# XentrinoBoard-ESP32-WROOM-2WD-2020_v1_2.net
KiCad netlist of a schematic drawn in EasyEDA
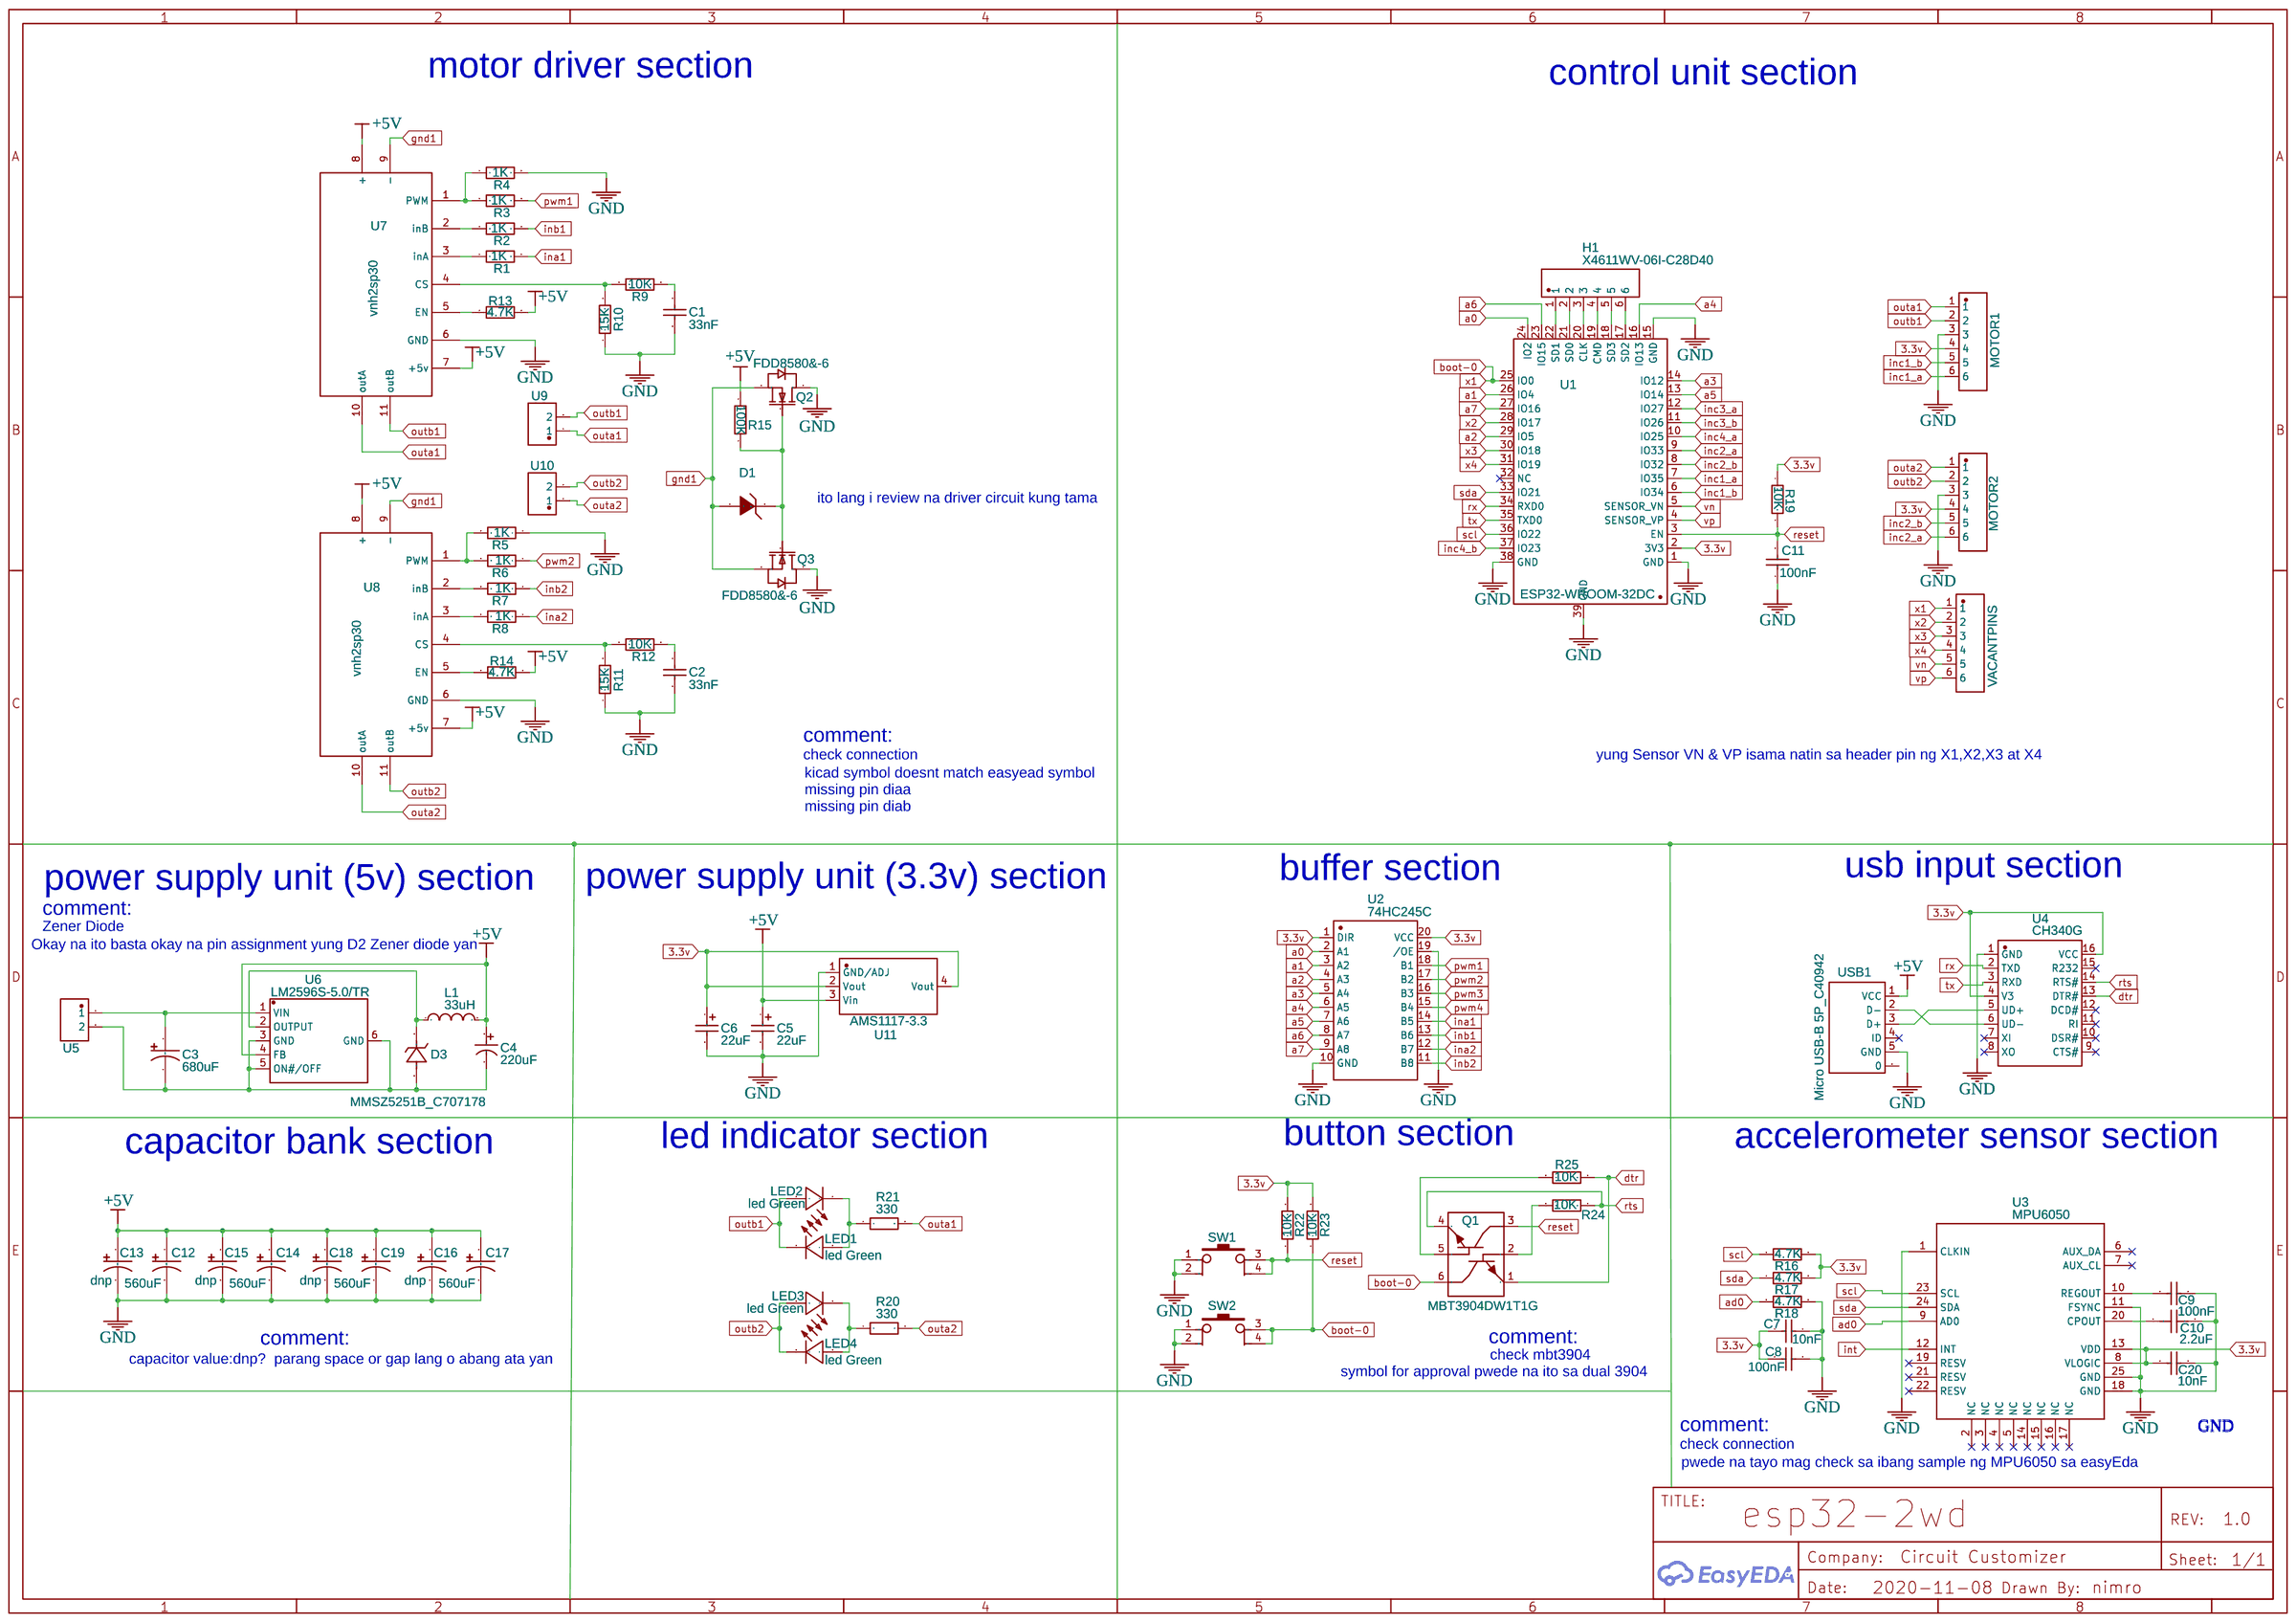
[diagram p0: schematic sheet]

(export (version "E")
  (design (tool "Eeschema 10.0.6"))
  (components
    (comp (ref "C1")
      (value "33nF")
      (fields
        (field (name "BOM_Manufacturer Part") "0805B333K500NT")
        (field (name "BOM_Supplier Part") "C1739")
      )
      (libsource (lib "") (part "0805B333K500NT"))
    )
    (comp (ref "C2")
      (value "33nF")
      (fields
        (field (name "BOM_Manufacturer Part") "0805B333K500NT")
        (field (name "BOM_Supplier Part") "C1739")
      )
      (libsource (lib "") (part "0805B333K500NT"))
    )
    (comp (ref "C3")
      (value "680uF")
      (fields
        (field (name "BOM_Manufacturer Part") "EEEFK1E681SP")
        (field (name "BOM_Supplier Part") "C413667")
      )
      (libsource (lib "") (part "EEEFK1E681SP"))
    )
    (comp (ref "C4")
      (value "220uF")
      (fields
        (field (name "BOM_Manufacturer Part") "DV221M025F105R")
        (field (name "BOM_Supplier Part") "C65222")
      )
      (libsource (lib "") (part "DV221M025F105R"))
    )
    (comp (ref "C5")
      (value "22uF")
      (fields
        (field (name "BOM_Manufacturer Part") "TAJA226K006RNJ")
        (field (name "BOM_Supplier Part") "C7182")
      )
      (libsource (lib "") (part "TAJA226K006RNJ"))
    )
    (comp (ref "C6")
      (value "22uF")
      (fields
        (field (name "BOM_Manufacturer Part") "TAJA226K006RNJ")
        (field (name "BOM_Supplier Part") "C7182")
      )
      (libsource (lib "") (part "TAJA226K006RNJ"))
    )
    (comp (ref "C7")
      (value "10nF")
      (fields
        (field (name "BOM_Manufacturer Part") "CL21C103JBFNNNE")
        (field (name "BOM_Supplier Part") "C27071")
      )
      (libsource (lib "") (part "CL21C103JBFNNNE"))
    )
    (comp (ref "C8")
      (value "100nF")
      (fields
        (field (name "BOM_Manufacturer Part") "CL21B104JBCNNNC")
        (field (name "BOM_Supplier Part") "C62912")
      )
      (libsource (lib "") (part "CL21B104JBCNNNC"))
    )
    (comp (ref "C9")
      (value "100nF")
      (fields
        (field (name "BOM_Manufacturer Part") "CL21B104JBCNNNC")
        (field (name "BOM_Supplier Part") "C62912")
      )
      (libsource (lib "") (part "CL21B104JBCNNNC"))
    )
    (comp (ref "C10")
      (value "2.2uF")
      (fields
        (field (name "BOM_Manufacturer Part") "CL10A225KA8NNNC")
        (field (name "BOM_Supplier Part") "C57895")
      )
      (libsource (lib "") (part "CL10A225KA8NNNC"))
    )
    (comp (ref "C11")
      (value "100nF")
      (fields
        (field (name "BOM_Manufacturer Part") "CL21B104JBCNNNC")
        (field (name "BOM_Supplier Part") "C62912")
      )
      (libsource (lib "") (part "CL21B104JBCNNNC_1"))
    )
    (comp (ref "C12")
      (value "560uF")
      (fields
        (field (name "BOM_Manufacturer Part") "PC0J561ME080A00CR0")
        (field (name "BOM_Supplier Part") "C190902")
      )
      (libsource (lib "") (part "PC0J561ME080A00CR0_1"))
    )
    (comp (ref "C13")
      (value "dnp")
      (fields
        (field (name "BOM_Manufacturer Part") "PC0J561ME080A00CR0")
        (field (name "BOM_Supplier Part") "C190902")
      )
      (libsource (lib "") (part "PC0J561ME080A00CR0_1"))
    )
    (comp (ref "C14")
      (value "560uF")
      (fields
        (field (name "BOM_Manufacturer Part") "PC0J561ME080A00CR0")
        (field (name "BOM_Supplier Part") "C190902")
      )
      (libsource (lib "") (part "PC0J561ME080A00CR0_1"))
    )
    (comp (ref "C15")
      (value "dnp")
      (fields
        (field (name "BOM_Manufacturer Part") "PC0J561ME080A00CR0")
        (field (name "BOM_Supplier Part") "C190902")
      )
      (libsource (lib "") (part "PC0J561ME080A00CR0_1"))
    )
    (comp (ref "C16")
      (value "dnp")
      (fields
        (field (name "BOM_Manufacturer Part") "PC0J561ME080A00CR0")
        (field (name "BOM_Supplier Part") "C190902")
      )
      (libsource (lib "") (part "PC0J561ME080A00CR0"))
    )
    (comp (ref "C17")
      (value "560uF")
      (fields
        (field (name "BOM_Manufacturer Part") "PC0J561ME080A00CR0")
        (field (name "BOM_Supplier Part") "C190902")
      )
      (libsource (lib "") (part "PC0J561ME080A00CR0"))
    )
    (comp (ref "C18")
      (value "dnp")
      (fields
        (field (name "BOM_Manufacturer Part") "PC0J561ME080A00CR0")
        (field (name "BOM_Supplier Part") "C190902")
      )
      (libsource (lib "") (part "PC0J561ME080A00CR0_1"))
    )
    (comp (ref "C19")
      (value "560uF")
      (fields
        (field (name "BOM_Manufacturer Part") "PC0J561ME080A00CR0")
        (field (name "BOM_Supplier Part") "C190902")
      )
      (libsource (lib "") (part "PC0J561ME080A00CR0_1"))
    )
    (comp (ref "C20")
      (value "10nF")
      (fields
        (field (name "BOM_Manufacturer Part") "CL21B104JBCNNNC")
        (field (name "BOM_Supplier Part") "C62912")
      )
      (libsource (lib "") (part "CL21B104JBCNNNC"))
    )
    (comp (ref "D1")
      (value "BZT52C2V7-7-F")
      (fields (field (name "BOM_Supplier Part") "C151624"))
      (libsource (lib "") (part "BZT52C2V7-7-F"))
    )
    (comp (ref "D3")
      (value "MMSZ5251B_C707178")
      (fields (field (name "BOM_Manufacturer Part") "MMSZ5251B") (field (name "BOM_Supplier Part") "C707178"))
      (libsource (lib "") (part "MMSZ5251B_C707178"))
    )
    (comp (ref "H1")
      (value "X4611WV-06I-C28D40")
      (fields (field (name "BOM_Supplier Part") "C706993"))
      (libsource (lib "") (part "X4611WV-06I-C28D40_2"))
    )
    (comp (ref "L1")
      (value "33uH")
      (fields
        (field (name "BOM_Manufacturer Part") "SWPA8040S330MT")
        (field (name "BOM_Supplier Part") "C83467")
      )
      (libsource (lib "") (part "SWPA8040S330MT"))
    )
    (comp (ref "LED1")
      (value "led Green")
      (fields (field (name "BOM_Supplier Part") "C14641"))
      (libsource (lib "") (part "led Green_1"))
    )
    (comp (ref "LED2")
      (value "led Green")
      (fields (field (name "BOM_Supplier Part") "C14641"))
      (libsource (lib "") (part "led Green"))
    )
    (comp (ref "LED3")
      (value "led Green")
      (fields (field (name "BOM_Supplier Part") "C14641"))
      (libsource (lib "") (part "led Green"))
    )
    (comp (ref "LED4")
      (value "led Green")
      (fields (field (name "BOM_Supplier Part") "C14641"))
      (libsource (lib "") (part "led Green_1"))
    )
    (comp (ref "MOTOR1")
      (value "X4611WV-06I-C28D40")
      (fields (field (name "BOM_Supplier Part") "C706993"))
      (libsource (lib "") (part "X4611WV-06I-C28D40"))
    )
    (comp (ref "MOTOR2")
      (value "X4611WV-06I-C28D40")
      (fields (field (name "BOM_Supplier Part") "C706993"))
      (libsource (lib "") (part "X4611WV-06I-C28D40"))
    )
    (comp (ref "Q1")
      (value "MBT3904DW1T1G")
      (fields (field (name "BOM_Supplier Part") "C110150"))
      (libsource (lib "") (part "MBT3904DW1T1G"))
    )
    (comp (ref "Q2")
      (value "FDD8580&-6")
      (fields (field (name "BOM_Supplier Part") "C693389"))
      (libsource (lib "") (part "FDD8580&amp;-6_1"))
    )
    (comp (ref "Q3")
      (value "FDD8580&-6")
      (fields (field (name "BOM_Supplier Part") "C693389"))
      (libsource (lib "") (part "FDD8580&amp;-6"))
    )
    (comp (ref "R1")
      (value "1K")
      (fields
        (field (name "BOM_Manufacturer Part") "RT0805FRD071KL")
        (field (name "BOM_Supplier Part") "C136907")
      )
      (libsource (lib "") (part "RT0805FRD071KL"))
    )
    (comp (ref "R2")
      (value "1K")
      (fields
        (field (name "BOM_Manufacturer Part") "RT0805FRD071KL")
        (field (name "BOM_Supplier Part") "C136907")
      )
      (libsource (lib "") (part "RT0805FRD071KL"))
    )
    (comp (ref "R3")
      (value "1K")
      (fields
        (field (name "BOM_Manufacturer Part") "RT0805FRD071KL")
        (field (name "BOM_Supplier Part") "C136907")
      )
      (libsource (lib "") (part "RT0805FRD071KL"))
    )
    (comp (ref "R4")
      (value "1K")
      (fields
        (field (name "BOM_Manufacturer Part") "RT0805FRD071KL")
        (field (name "BOM_Supplier Part") "C136907")
      )
      (libsource (lib "") (part "RT0805FRD071KL"))
    )
    (comp (ref "R5")
      (value "1K")
      (fields
        (field (name "BOM_Manufacturer Part") "RT0805FRD071KL")
        (field (name "BOM_Supplier Part") "C136907")
      )
      (libsource (lib "") (part "RT0805FRD071KL_1"))
    )
    (comp (ref "R6")
      (value "1K")
      (fields
        (field (name "BOM_Manufacturer Part") "RT0805FRD071KL")
        (field (name "BOM_Supplier Part") "C136907")
      )
      (libsource (lib "") (part "RT0805FRD071KL_1"))
    )
    (comp (ref "R7")
      (value "1K")
      (fields
        (field (name "BOM_Manufacturer Part") "RT0805FRD071KL")
        (field (name "BOM_Supplier Part") "C136907")
      )
      (libsource (lib "") (part "RT0805FRD071KL_1"))
    )
    (comp (ref "R8")
      (value "1K")
      (fields
        (field (name "BOM_Manufacturer Part") "RT0805FRD071KL")
        (field (name "BOM_Supplier Part") "C136907")
      )
      (libsource (lib "") (part "RT0805FRD071KL_1"))
    )
    (comp (ref "R9")
      (value "10K")
      (fields
        (field (name "BOM_Manufacturer Part") "LE03WAJ0103T5E")
        (field (name "BOM_Supplier Part") "C81087")
      )
      (libsource (lib "") (part "LE03WAJ0103T5E"))
    )
    (comp (ref "R10")
      (value "15K")
      (fields
        (field (name "BOM_Manufacturer Part") "RK73H2ATTD1502F")
        (field (name "BOM_Supplier Part") "C160068")
      )
      (libsource (lib "") (part "RK73H2ATTD1502F"))
    )
    (comp (ref "R11")
      (value "15K")
      (fields
        (field (name "BOM_Manufacturer Part") "RK73H2ATTD1502F")
        (field (name "BOM_Supplier Part") "C160068")
      )
      (libsource (lib "") (part "RK73H2ATTD1502F"))
    )
    (comp (ref "R12")
      (value "10K")
      (fields
        (field (name "BOM_Manufacturer Part") "LE03WAJ0103T5E")
        (field (name "BOM_Supplier Part") "C81087")
      )
      (libsource (lib "") (part "LE03WAJ0103T5E"))
    )
    (comp (ref "R13")
      (value "4.7K")
      (fields
        (field (name "BOM_Manufacturer Part") "RC0603JR-074K7L")
        (field (name "BOM_Supplier Part") "C105428")
      )
      (libsource (lib "") (part "RC0603JR-074K7L"))
    )
    (comp (ref "R14")
      (value "4.7K")
      (fields
        (field (name "BOM_Manufacturer Part") "RC0603JR-074K7L")
        (field (name "BOM_Supplier Part") "C105428")
      )
      (libsource (lib "") (part "RC0603JR-074K7L"))
    )
    (comp (ref "R15")
      (value "100K")
      (fields
        (field (name "BOM_Manufacturer Part") "MCWF08U1003BTL")
        (field (name "BOM_Supplier Part") "C241287")
      )
      (libsource (lib "") (part "MCWF08U1003BTL"))
    )
    (comp (ref "R16")
      (value "4.7K")
      (fields
        (field (name "BOM_Manufacturer Part") "RC0603JR-074K7L")
        (field (name "BOM_Supplier Part") "C105428")
      )
      (libsource (lib "") (part "RC0603JR-074K7L"))
    )
    (comp (ref "R17")
      (value "4.7K")
      (fields
        (field (name "BOM_Manufacturer Part") "RC0603JR-074K7L")
        (field (name "BOM_Supplier Part") "C105428")
      )
      (libsource (lib "") (part "RC0603JR-074K7L"))
    )
    (comp (ref "R18")
      (value "4.7K")
      (fields
        (field (name "BOM_Manufacturer Part") "RC0603JR-074K7L")
        (field (name "BOM_Supplier Part") "C105428")
      )
      (libsource (lib "") (part "RC0603JR-074K7L"))
    )
    (comp (ref "R19")
      (value "10K")
      (fields
        (field (name "BOM_Manufacturer Part") "LE03WAJ0103T5E")
        (field (name "BOM_Supplier Part") "C81087")
      )
      (libsource (lib "") (part "LE03WAJ0103T5E_3"))
    )
    (comp (ref "R20")
      (value "330")
      (fields
        (field (name "BOM_Manufacturer Part") "330R 5% 0603")
        (field (name "BOM_Supplier Part") "C22104")
      )
      (libsource (lib "") (part "330R 5% 0603"))
    )
    (comp (ref "R21")
      (value "330")
      (fields
        (field (name "BOM_Manufacturer Part") "330R 5% 0603")
        (field (name "BOM_Supplier Part") "C22104")
      )
      (libsource (lib "") (part "330R 5% 0603"))
    )
    (comp (ref "R22")
      (value "10K")
      (fields
        (field (name "BOM_Manufacturer Part") "LE03WAJ0103T5E")
        (field (name "BOM_Supplier Part") "C81087")
      )
      (libsource (lib "") (part "LE03WAJ0103T5E_2"))
    )
    (comp (ref "R23")
      (value "10K")
      (fields
        (field (name "BOM_Manufacturer Part") "LE03WAJ0103T5E")
        (field (name "BOM_Supplier Part") "C81087")
      )
      (libsource (lib "") (part "LE03WAJ0103T5E_2"))
    )
    (comp (ref "R24")
      (value "10K")
      (fields
        (field (name "BOM_Manufacturer Part") "LE03WAJ0103T5E")
        (field (name "BOM_Supplier Part") "C81087")
      )
      (libsource (lib "") (part "LE03WAJ0103T5E_1"))
    )
    (comp (ref "R25")
      (value "10K")
      (fields
        (field (name "BOM_Manufacturer Part") "LE03WAJ0103T5E")
        (field (name "BOM_Supplier Part") "C81087")
      )
      (libsource (lib "") (part "LE03WAJ0103T5E_1"))
    )
    (comp (ref "SW1")
      (value "Button-SMD-4.5x4.5x5.5")
      (fields
        (field (name "BOM_Manufacturer Part") "4.5*4.5*5.5 Plastic head,260G, 0.25mm,SMD")
        (field (name "BOM_Supplier Part") "C71849")
      )
      (libsource (lib "") (part "Button-SMD-4.5x4.5x5.5"))
    )
    (comp (ref "SW2")
      (value "Button-SMD-4.5x4.5x5.5")
      (fields
        (field (name "BOM_Manufacturer Part") "4.5*4.5*5.5 Plastic head,260G, 0.25mm,SMD")
        (field (name "BOM_Supplier Part") "C71849")
      )
      (libsource (lib "") (part "Button-SMD-4.5x4.5x5.5"))
    )
    (comp (ref "U1")
      (value "ESP32-WROOM-32DC")
      (fields (field (name "BOM_Supplier Part") "C473013"))
      (libsource (lib "") (part "ESP32-WROOM-32DC"))
    )
    (comp (ref "U2")
      (value "74HC245C")
      (fields (field (name "BOM_Supplier Part") "C126198"))
      (libsource (lib "") (part "74HC245C"))
    )
    (comp (ref "U3") (value "MPU6050") (libsource (lib "") (part "MPU6050")))
    (comp (ref "U4")
      (value "CH340G")
      (fields (field (name "BOM_Supplier Part") "C14267"))
      (libsource (lib "") (part "CH340G"))
    )
    (comp (ref "U5")
      (value "ED555/2DS")
      (fields (field (name "BOM_Supplier Part") "C98754"))
      (libsource (lib "") (part "ED555/2DS_1"))
    )
    (comp (ref "U6")
      (value "LM2596S-5.0/TR")
      (fields (field (name "BOM_Supplier Part") "C194349"))
      (libsource (lib "") (part "LM2596S-5.0/TR"))
    )
    (comp (ref "U7") (value "vnh2sp30") (libsource (lib "") (part "vnh2sp30")))
    (comp (ref "U8") (value "vnh2sp30") (libsource (lib "") (part "vnh2sp30")))
    (comp (ref "U9")
      (value "ED555/2DS")
      (fields (field (name "BOM_Supplier Part") "C98754"))
      (libsource (lib "") (part "ED555/2DS"))
    )
    (comp (ref "U10")
      (value "ED555/2DS")
      (fields (field (name "BOM_Supplier Part") "C98754"))
      (libsource (lib "") (part "ED555/2DS"))
    )
    (comp (ref "U11")
      (value "AMS1117-3.3")
      (fields (field (name "BOM_Supplier Part") "C6186"))
      (libsource (lib "") (part "AMS1117-3.3"))
    )
    (comp (ref "USB1")
      (value "Micro USB-B 5P_C40942")
      (fields (field (name "BOM_Supplier Part") "C40942"))
      (libsource (lib "") (part "Micro USB-B 5P_C40942"))
    )
    (comp (ref "VACANTPINS")
      (value "X4611WV-06I-C28D40")
      (fields (field (name "BOM_Supplier Part") "C706993"))
      (libsource (lib "") (part "X4611WV-06I-C28D40_1"))
    )
  )
  (nets
    (net (code "1") (name "+5V") (class "Default")
      (node (ref "C12") (pin "1") (pinfunction "1_1") (pintype "unspecified"))
      (node (ref "C13") (pin "1") (pinfunction "1_1") (pintype "unspecified"))
      (node (ref "C14") (pin "1") (pinfunction "1_1") (pintype "unspecified"))
      (node (ref "C15") (pin "1") (pinfunction "1_1") (pintype "unspecified"))
      (node (ref "C16") (pin "1") (pinfunction "1_1") (pintype "unspecified"))
      (node (ref "C17") (pin "1") (pinfunction "1_1") (pintype "unspecified"))
      (node (ref "C18") (pin "1") (pinfunction "1_1") (pintype "unspecified"))
      (node (ref "C19") (pin "1") (pinfunction "1_1") (pintype "unspecified"))
      (node (ref "C4") (pin "1") (pinfunction "1_1") (pintype "input"))
      (node (ref "C5") (pin "1") (pinfunction "1_1") (pintype "input"))
      (node (ref "L1") (pin "2") (pinfunction "2_2") (pintype "unspecified"))
      (node (ref "R13") (pin "2") (pinfunction "2_2") (pintype "input"))
      (node (ref "R14") (pin "2") (pinfunction "2_2") (pintype "input"))
      (node (ref "R15") (pin "2") (pinfunction "2_2") (pintype "unspecified"))
      (node (ref "U11") (pin "3") (pinfunction "Vin_3") (pintype "unspecified"))
      (node (ref "U6") (pin "4") (pinfunction "FB_4") (pintype "unspecified"))
      (node (ref "U7") (pin "7") (pinfunction "+5v_7") (pintype "unspecified"))
      (node (ref "U7") (pin "8") (pinfunction "+_8") (pintype "unspecified"))
      (node (ref "U8") (pin "7") (pinfunction "+5v_7") (pintype "unspecified"))
      (node (ref "U8") (pin "8") (pinfunction "+_8") (pintype "unspecified"))
      (node (ref "USB1") (pin "1") (pinfunction "VCC_1") (pintype "input"))
    )
    (net (code "2") (name "3.3v") (class "Default")
      (node (ref "C20") (pin "1") (pinfunction "1_1") (pintype "input"))
      (node (ref "C6") (pin "1") (pinfunction "1_1") (pintype "input"))
      (node (ref "C7") (pin "1") (pinfunction "1_1") (pintype "input"))
      (node (ref "C8") (pin "1") (pinfunction "1_1") (pintype "input"))
      (node (ref "MOTOR1") (pin "4") (pinfunction "4_4") (pintype "unspecified"))
      (node (ref "MOTOR2") (pin "4") (pinfunction "4_4") (pintype "unspecified"))
      (node (ref "R16") (pin "2") (pinfunction "2_2") (pintype "input"))
      (node (ref "R17") (pin "2") (pinfunction "2_2") (pintype "input"))
      (node (ref "R19") (pin "1") (pinfunction "1_1") (pintype "input"))
      (node (ref "R22") (pin "2") (pinfunction "2_2") (pintype "input"))
      (node (ref "R23") (pin "2") (pinfunction "2_2") (pintype "input"))
      (node (ref "U1") (pin "2") (pinfunction "3V3_2") (pintype "unspecified"))
      (node (ref "U11") (pin "2") (pinfunction "Vout_2") (pintype "unspecified"))
      (node (ref "U11") (pin "4") (pinfunction "Vout_4") (pintype "unspecified"))
      (node (ref "U2") (pin "1") (pinfunction "DIR_1") (pintype "unspecified"))
      (node (ref "U2") (pin "20") (pinfunction "VCC_20") (pintype "unspecified"))
      (node (ref "U3") (pin "13") (pinfunction "VDD_13") (pintype "passive"))
      (node (ref "U3") (pin "8") (pinfunction "VLOGIC_8") (pintype "passive"))
      (node (ref "U4") (pin "16") (pinfunction "VCC_16") (pintype "unspecified"))
      (node (ref "U4") (pin "4") (pinfunction "V3_4") (pintype "unspecified"))
    )
    (net (code "3") (name "GND") (class "Default")
      (node (ref "C1") (pin "1") (pinfunction "1_1") (pintype "input"))
      (node (ref "C10") (pin "2") (pinfunction "2_2") (pintype "unspecified"))
      (node (ref "C11") (pin "1") (pinfunction "1_1") (pintype "input"))
      (node (ref "C12") (pin "2") (pinfunction "2_2") (pintype "unspecified"))
      (node (ref "C13") (pin "2") (pinfunction "2_2") (pintype "unspecified"))
      (node (ref "C14") (pin "2") (pinfunction "2_2") (pintype "unspecified"))
      (node (ref "C15") (pin "2") (pinfunction "2_2") (pintype "unspecified"))
      (node (ref "C16") (pin "2") (pinfunction "2_2") (pintype "unspecified"))
      (node (ref "C17") (pin "2") (pinfunction "2_2") (pintype "unspecified"))
      (node (ref "C18") (pin "2") (pinfunction "2_2") (pintype "unspecified"))
      (node (ref "C19") (pin "2") (pinfunction "2_2") (pintype "unspecified"))
      (node (ref "C2") (pin "1") (pinfunction "1_1") (pintype "input"))
      (node (ref "C20") (pin "2") (pinfunction "2_2") (pintype "input"))
      (node (ref "C5") (pin "2") (pinfunction "2_2") (pintype "input"))
      (node (ref "C6") (pin "2") (pinfunction "2_2") (pintype "input"))
      (node (ref "C7") (pin "2") (pinfunction "2_2") (pintype "input"))
      (node (ref "C8") (pin "2") (pinfunction "2_2") (pintype "input"))
      (node (ref "C9") (pin "2") (pinfunction "2_2") (pintype "input"))
      (node (ref "MOTOR1") (pin "3") (pinfunction "3_3") (pintype "unspecified"))
      (node (ref "MOTOR2") (pin "3") (pinfunction "3_3") (pintype "unspecified"))
      (node (ref "Q2") (pin "2") (pinfunction "D_2") (pintype "unspecified"))
      (node (ref "Q3") (pin "2") (pinfunction "D_2") (pintype "unspecified"))
      (node (ref "R10") (pin "1") (pinfunction "1_1") (pintype "unspecified"))
      (node (ref "R11") (pin "1") (pinfunction "1_1") (pintype "unspecified"))
      (node (ref "R18") (pin "2") (pinfunction "2_2") (pintype "input"))
      (node (ref "R4") (pin "2") (pinfunction "2_2") (pintype "unspecified"))
      (node (ref "R5") (pin "1") (pinfunction "1_1") (pintype "unspecified"))
      (node (ref "SW1") (pin "1") (pinfunction "1_1") (pintype "input"))
      (node (ref "SW1") (pin "2") (pinfunction "2_2") (pintype "input"))
      (node (ref "SW2") (pin "1") (pinfunction "1_1") (pintype "input"))
      (node (ref "SW2") (pin "2") (pinfunction "2_2") (pintype "input"))
      (node (ref "U1") (pin "1") (pinfunction "GND_1") (pintype "unspecified"))
      (node (ref "U1") (pin "15") (pinfunction "GND_15") (pintype "unspecified"))
      (node (ref "U1") (pin "38") (pinfunction "GND_38") (pintype "unspecified"))
      (node (ref "U1") (pin "39") (pinfunction "GND_39") (pintype "unspecified"))
      (node (ref "U11") (pin "1") (pinfunction "GND/ADJ_1") (pintype "unspecified"))
      (node (ref "U2") (pin "10") (pinfunction "GND_10") (pintype "unspecified"))
      (node (ref "U2") (pin "19") (pinfunction "/OE_19") (pintype "unspecified"))
      (node (ref "U3") (pin "1") (pinfunction "CLKIN_1") (pintype "input"))
      (node (ref "U3") (pin "11") (pinfunction "FSYNC_11") (pintype "input"))
      (node (ref "U3") (pin "18") (pinfunction "GND_18") (pintype "passive"))
      (node (ref "U3") (pin "25") (pinfunction "GND_25") (pintype "passive"))
      (node (ref "U4") (pin "1") (pinfunction "GND_1") (pintype "unspecified"))
      (node (ref "U7") (pin "6") (pinfunction "GND_6") (pintype "unspecified"))
      (node (ref "U8") (pin "6") (pinfunction "GND_6") (pintype "unspecified"))
      (node (ref "USB1") (pin "5") (pinfunction "GND_5") (pintype "input"))
    )
    (net (code "4") (name "Net-(C1-Pad2)") (class "Default")
      (node (ref "C1") (pin "2") (pinfunction "2_2") (pintype "input"))
      (node (ref "R9") (pin "2") (pinfunction "2_2") (pintype "input"))
    )
    (net (code "5") (name "Net-(C2-Pad2)") (class "Default")
      (node (ref "C2") (pin "2") (pinfunction "2_2") (pintype "input"))
      (node (ref "R12") (pin "2") (pinfunction "2_2") (pintype "input"))
    )
    (net (code "6") (name "Net-(D1-K)") (class "Default")
      (node (ref "D1") (pin "1") (pinfunction "K_1") (pintype "unspecified"))
      (node (ref "Q2") (pin "1") (pinfunction "G_1") (pintype "unspecified"))
      (node (ref "Q3") (pin "1") (pinfunction "G_1") (pintype "unspecified"))
      (node (ref "R15") (pin "1") (pinfunction "1_1") (pintype "unspecified"))
    )
    (net (code "7") (name "Net-(D3-A)") (class "Default")
      (node (ref "C3") (pin "2") (pinfunction "2_2") (pintype "unspecified"))
      (node (ref "C4") (pin "2") (pinfunction "2_2") (pintype "input"))
      (node (ref "D3") (pin "2") (pinfunction "A_2") (pintype "unspecified"))
      (node (ref "U5") (pin "2") (pinfunction "2_2") (pintype "unspecified"))
      (node (ref "U6") (pin "3") (pinfunction "GND_3") (pintype "unspecified"))
      (node (ref "U6") (pin "5") (pinfunction "ON#/OFF_5") (pintype "unspecified"))
      (node (ref "U6") (pin "6") (pinfunction "GND_6") (pintype "unspecified"))
    )
    (net (code "8") (name "Net-(D3-K)") (class "Default")
      (node (ref "D3") (pin "1") (pinfunction "K_1") (pintype "unspecified"))
      (node (ref "L1") (pin "1") (pinfunction "1_1") (pintype "unspecified"))
      (node (ref "U6") (pin "2") (pinfunction "OUTPUT_2") (pintype "unspecified"))
    )
    (net (code "9") (name "Net-(LED1-+)") (class "Default")
      (node (ref "LED1") (pin "2") (pinfunction "+_2") (pintype "unspecified"))
      (node (ref "LED2") (pin "1") (pinfunction "-_1") (pintype "unspecified"))
      (node (ref "R21") (pin "1") (pinfunction "1_1") (pintype "input"))
    )
    (net (code "10") (name "Net-(LED3--)") (class "Default")
      (node (ref "LED3") (pin "1") (pinfunction "-_1") (pintype "unspecified"))
      (node (ref "LED4") (pin "2") (pinfunction "+_2") (pintype "unspecified"))
      (node (ref "R20") (pin "1") (pinfunction "1_1") (pintype "input"))
    )
    (net (code "11") (name "Net-(Q1-Pad2)") (class "Default")
      (node (ref "Q1") (pin "2") (pinfunction "2_2") (pintype "input"))
      (node (ref "R24") (pin "2") (pinfunction "2_2") (pintype "input"))
    )
    (net (code "12") (name "Net-(Q1-Pad5)") (class "Default")
      (node (ref "Q1") (pin "5") (pinfunction "5_5") (pintype "input"))
      (node (ref "R25") (pin "2") (pinfunction "2_2") (pintype "input"))
    )
    (net (code "13") (name "Net-(U1-CLK)") (class "Default")
      (node (ref "H1") (pin "3") (pinfunction "3_3") (pintype "unspecified"))
      (node (ref "U1") (pin "20") (pinfunction "CLK_20") (pintype "unspecified"))
    )
    (net (code "14") (name "Net-(U1-CMD)") (class "Default")
      (node (ref "H1") (pin "4") (pinfunction "4_4") (pintype "unspecified"))
      (node (ref "U1") (pin "19") (pinfunction "CMD_19") (pintype "unspecified"))
    )
    (net (code "15") (name "Net-(U1-SD0)") (class "Default")
      (node (ref "H1") (pin "2") (pinfunction "2_2") (pintype "unspecified"))
      (node (ref "U1") (pin "21") (pinfunction "SD0_21") (pintype "unspecified"))
    )
    (net (code "16") (name "Net-(U1-SD1)") (class "Default")
      (node (ref "H1") (pin "1") (pinfunction "1_1") (pintype "unspecified"))
      (node (ref "U1") (pin "22") (pinfunction "SD1_22") (pintype "unspecified"))
    )
    (net (code "17") (name "Net-(U1-SD2)") (class "Default")
      (node (ref "H1") (pin "6") (pinfunction "6_6") (pintype "unspecified"))
      (node (ref "U1") (pin "17") (pinfunction "SD2_17") (pintype "unspecified"))
    )
    (net (code "18") (name "Net-(U1-SD3)") (class "Default")
      (node (ref "H1") (pin "5") (pinfunction "5_5") (pintype "unspecified"))
      (node (ref "U1") (pin "18") (pinfunction "SD3_18") (pintype "unspecified"))
    )
    (net (code "19") (name "Net-(U3-CPOUT)") (class "Default")
      (node (ref "C10") (pin "1") (pinfunction "1_1") (pintype "unspecified"))
      (node (ref "U3") (pin "20") (pinfunction "CPOUT_20") (pintype "output"))
    )
    (net (code "20") (name "Net-(U3-REGOUT)") (class "Default")
      (node (ref "C9") (pin "1") (pinfunction "1_1") (pintype "input"))
      (node (ref "U3") (pin "10") (pinfunction "REGOUT_10") (pintype "output"))
    )
    (net (code "21") (name "Net-(U4-UD+)") (class "Default")
      (node (ref "U4") (pin "5") (pinfunction "UD+_5") (pintype "unspecified"))
      (node (ref "USB1") (pin "3") (pinfunction "D+_3") (pintype "input"))
    )
    (net (code "22") (name "Net-(U4-UD-)") (class "Default")
      (node (ref "U4") (pin "6") (pinfunction "UD-_6") (pintype "unspecified"))
      (node (ref "USB1") (pin "2") (pinfunction "D-_2") (pintype "input"))
    )
    (net (code "23") (name "Net-(U6-VIN)") (class "Default")
      (node (ref "C3") (pin "1") (pinfunction "1_1") (pintype "unspecified"))
      (node (ref "U5") (pin "1") (pinfunction "1_1") (pintype "unspecified"))
      (node (ref "U6") (pin "1") (pinfunction "VIN_1") (pintype "unspecified"))
    )
    (net (code "24") (name "Net-(U7-CS)") (class "Default")
      (node (ref "R10") (pin "2") (pinfunction "2_2") (pintype "unspecified"))
      (node (ref "R9") (pin "1") (pinfunction "1_1") (pintype "input"))
      (node (ref "U7") (pin "4") (pinfunction "CS_4") (pintype "unspecified"))
    )
    (net (code "25") (name "Net-(U7-EN)") (class "Default")
      (node (ref "R13") (pin "1") (pinfunction "1_1") (pintype "input"))
      (node (ref "U7") (pin "5") (pinfunction "EN_5") (pintype "unspecified"))
    )
    (net (code "26") (name "Net-(U7-PWM)") (class "Default")
      (node (ref "R3") (pin "1") (pinfunction "1_1") (pintype "unspecified"))
      (node (ref "R4") (pin "1") (pinfunction "1_1") (pintype "unspecified"))
      (node (ref "U7") (pin "1") (pinfunction "PWM_1") (pintype "unspecified"))
    )
    (net (code "27") (name "Net-(U7-inA)") (class "Default")
      (node (ref "R1") (pin "1") (pinfunction "1_1") (pintype "unspecified"))
      (node (ref "U7") (pin "3") (pinfunction "inA_3") (pintype "unspecified"))
    )
    (net (code "28") (name "Net-(U7-inB)") (class "Default")
      (node (ref "R2") (pin "1") (pinfunction "1_1") (pintype "unspecified"))
      (node (ref "U7") (pin "2") (pinfunction "inB_2") (pintype "unspecified"))
    )
    (net (code "29") (name "Net-(U8-CS)") (class "Default")
      (node (ref "R11") (pin "2") (pinfunction "2_2") (pintype "unspecified"))
      (node (ref "R12") (pin "1") (pinfunction "1_1") (pintype "input"))
      (node (ref "U8") (pin "4") (pinfunction "CS_4") (pintype "unspecified"))
    )
    (net (code "30") (name "Net-(U8-EN)") (class "Default")
      (node (ref "R14") (pin "1") (pinfunction "1_1") (pintype "input"))
      (node (ref "U8") (pin "5") (pinfunction "EN_5") (pintype "unspecified"))
    )
    (net (code "31") (name "Net-(U8-PWM)") (class "Default")
      (node (ref "R5") (pin "2") (pinfunction "2_2") (pintype "unspecified"))
      (node (ref "R6") (pin "2") (pinfunction "2_2") (pintype "unspecified"))
      (node (ref "U8") (pin "1") (pinfunction "PWM_1") (pintype "unspecified"))
    )
    (net (code "32") (name "Net-(U8-inA)") (class "Default")
      (node (ref "R8") (pin "2") (pinfunction "2_2") (pintype "unspecified"))
      (node (ref "U8") (pin "3") (pinfunction "inA_3") (pintype "unspecified"))
    )
    (net (code "33") (name "Net-(U8-inB)") (class "Default")
      (node (ref "R7") (pin "2") (pinfunction "2_2") (pintype "unspecified"))
      (node (ref "U8") (pin "2") (pinfunction "inB_2") (pintype "unspecified"))
    )
    (net (code "34") (name "a0") (class "Default")
      (node (ref "U1") (pin "24") (pinfunction "IO2_24") (pintype "unspecified"))
      (node (ref "U2") (pin "2") (pinfunction "A1_2") (pintype "unspecified"))
    )
    (net (code "35") (name "a1") (class "Default")
      (node (ref "U1") (pin "26") (pinfunction "IO4_26") (pintype "unspecified"))
      (node (ref "U2") (pin "3") (pinfunction "A2_3") (pintype "unspecified"))
    )
    (net (code "36") (name "a2") (class "Default")
      (node (ref "U1") (pin "29") (pinfunction "IO5_29") (pintype "unspecified"))
      (node (ref "U2") (pin "4") (pinfunction "A3_4") (pintype "unspecified"))
    )
    (net (code "37") (name "a3") (class "Default")
      (node (ref "U1") (pin "14") (pinfunction "IO12_14") (pintype "unspecified"))
      (node (ref "U2") (pin "5") (pinfunction "A4_5") (pintype "unspecified"))
    )
    (net (code "38") (name "a4") (class "Default")
      (node (ref "U1") (pin "16") (pinfunction "IO13_16") (pintype "unspecified"))
      (node (ref "U2") (pin "6") (pinfunction "A5_6") (pintype "unspecified"))
    )
    (net (code "39") (name "a5") (class "Default")
      (node (ref "U1") (pin "13") (pinfunction "IO14_13") (pintype "unspecified"))
      (node (ref "U2") (pin "7") (pinfunction "A6_7") (pintype "unspecified"))
    )
    (net (code "40") (name "a6") (class "Default")
      (node (ref "U1") (pin "23") (pinfunction "IO15_23") (pintype "unspecified"))
      (node (ref "U2") (pin "8") (pinfunction "A7_8") (pintype "unspecified"))
    )
    (net (code "41") (name "a7") (class "Default")
      (node (ref "U1") (pin "27") (pinfunction "IO16_27") (pintype "unspecified"))
      (node (ref "U2") (pin "9") (pinfunction "A8_9") (pintype "unspecified"))
    )
    (net (code "42") (name "ad0") (class "Default")
      (node (ref "R18") (pin "1") (pinfunction "1_1") (pintype "input"))
      (node (ref "U3") (pin "9") (pinfunction "AD0_9") (pintype "input"))
    )
    (net (code "43") (name "boot-0") (class "Default")
      (node (ref "Q1") (pin "6") (pinfunction "6_6") (pintype "input"))
      (node (ref "R23") (pin "1") (pinfunction "1_1") (pintype "input"))
      (node (ref "SW2") (pin "3") (pinfunction "3_3") (pintype "input"))
      (node (ref "SW2") (pin "4") (pinfunction "4_4") (pintype "input"))
      (node (ref "U1") (pin "25") (pinfunction "IO0_25") (pintype "unspecified"))
      (node (ref "VACANTPINS") (pin "1") (pinfunction "1_1") (pintype "unspecified"))
    )
    (net (code "44") (name "dtr") (class "Default")
      (node (ref "Q1") (pin "1") (pinfunction "1_1") (pintype "input"))
      (node (ref "R25") (pin "1") (pinfunction "1_1") (pintype "input"))
      (node (ref "U4") (pin "13") (pinfunction "DTR#_13") (pintype "unspecified"))
    )
    (net (code "45") (name "gnd1") (class "Default")
      (node (ref "D1") (pin "2") (pinfunction "A_2") (pintype "unspecified"))
      (node (ref "Q2") (pin "3") (pinfunction "S_3") (pintype "unspecified"))
      (node (ref "Q3") (pin "3") (pinfunction "S_3") (pintype "unspecified"))
      (node (ref "U7") (pin "9") (pinfunction "-_9") (pintype "unspecified"))
      (node (ref "U8") (pin "9") (pinfunction "-_9") (pintype "unspecified"))
    )
    (net (code "46") (name "ina1") (class "Default")
      (node (ref "R1") (pin "2") (pinfunction "2_2") (pintype "unspecified"))
      (node (ref "U2") (pin "14") (pinfunction "B5_14") (pintype "unspecified"))
    )
    (net (code "47") (name "ina2") (class "Default")
      (node (ref "R8") (pin "1") (pinfunction "1_1") (pintype "unspecified"))
      (node (ref "U2") (pin "12") (pinfunction "B7_12") (pintype "unspecified"))
    )
    (net (code "48") (name "inb1") (class "Default")
      (node (ref "R2") (pin "2") (pinfunction "2_2") (pintype "unspecified"))
      (node (ref "U2") (pin "13") (pinfunction "B6_13") (pintype "unspecified"))
    )
    (net (code "49") (name "inb2") (class "Default")
      (node (ref "R7") (pin "1") (pinfunction "1_1") (pintype "unspecified"))
      (node (ref "U2") (pin "11") (pinfunction "B8_11") (pintype "unspecified"))
    )
    (net (code "50") (name "inc1_a") (class "Default")
      (node (ref "MOTOR1") (pin "6") (pinfunction "6_6") (pintype "unspecified"))
      (node (ref "U1") (pin "7") (pinfunction "IO35_7") (pintype "unspecified"))
    )
    (net (code "51") (name "inc1_b") (class "Default")
      (node (ref "MOTOR1") (pin "5") (pinfunction "5_5") (pintype "unspecified"))
      (node (ref "U1") (pin "6") (pinfunction "IO34_6") (pintype "unspecified"))
    )
    (net (code "52") (name "inc2_a") (class "Default")
      (node (ref "MOTOR2") (pin "6") (pinfunction "6_6") (pintype "unspecified"))
      (node (ref "U1") (pin "9") (pinfunction "IO33_9") (pintype "unspecified"))
    )
    (net (code "53") (name "inc2_b") (class "Default")
      (node (ref "MOTOR2") (pin "5") (pinfunction "5_5") (pintype "unspecified"))
      (node (ref "U1") (pin "8") (pinfunction "IO32_8") (pintype "unspecified"))
    )
    (net (code "54") (name "inc3_a") (class "Default")
      (node (ref "U1") (pin "12") (pinfunction "IO27_12") (pintype "unspecified"))
    )
    (net (code "55") (name "inc3_b") (class "Default")
      (node (ref "U1") (pin "11") (pinfunction "IO26_11") (pintype "unspecified"))
    )
    (net (code "56") (name "inc4_a") (class "Default")
      (node (ref "U1") (pin "10") (pinfunction "IO25_10") (pintype "unspecified"))
    )
    (net (code "57") (name "inc4_b") (class "Default")
      (node (ref "U1") (pin "37") (pinfunction "IO23_37") (pintype "unspecified"))
    )
    (net (code "58") (name "int") (class "Default")
      (node (ref "U3") (pin "12") (pinfunction "INT_12") (pintype "unspecified"))
    )
    (net (code "59") (name "outa1") (class "Default")
      (node (ref "MOTOR1") (pin "1") (pinfunction "1_1") (pintype "unspecified"))
      (node (ref "R21") (pin "2") (pinfunction "2_2") (pintype "input"))
      (node (ref "U7") (pin "10") (pinfunction "outA_10") (pintype "unspecified"))
      (node (ref "U9") (pin "1") (pinfunction "1_1") (pintype "unspecified"))
    )
    (net (code "60") (name "outa2") (class "Default")
      (node (ref "MOTOR2") (pin "1") (pinfunction "1_1") (pintype "unspecified"))
      (node (ref "R20") (pin "2") (pinfunction "2_2") (pintype "input"))
      (node (ref "U10") (pin "1") (pinfunction "1_1") (pintype "unspecified"))
      (node (ref "U8") (pin "10") (pinfunction "outA_10") (pintype "unspecified"))
    )
    (net (code "61") (name "outb1") (class "Default")
      (node (ref "LED1") (pin "1") (pinfunction "-_1") (pintype "unspecified"))
      (node (ref "LED2") (pin "2") (pinfunction "+_2") (pintype "unspecified"))
      (node (ref "MOTOR1") (pin "2") (pinfunction "2_2") (pintype "unspecified"))
      (node (ref "U7") (pin "11") (pinfunction "outB_11") (pintype "unspecified"))
      (node (ref "U9") (pin "2") (pinfunction "2_2") (pintype "unspecified"))
    )
    (net (code "62") (name "outb2") (class "Default")
      (node (ref "LED3") (pin "2") (pinfunction "+_2") (pintype "unspecified"))
      (node (ref "LED4") (pin "1") (pinfunction "-_1") (pintype "unspecified"))
      (node (ref "MOTOR2") (pin "2") (pinfunction "2_2") (pintype "unspecified"))
      (node (ref "U10") (pin "2") (pinfunction "2_2") (pintype "unspecified"))
      (node (ref "U8") (pin "11") (pinfunction "outB_11") (pintype "unspecified"))
    )
    (net (code "63") (name "pwm1") (class "Default")
      (node (ref "R3") (pin "2") (pinfunction "2_2") (pintype "unspecified"))
      (node (ref "U2") (pin "18") (pinfunction "B1_18") (pintype "unspecified"))
    )
    (net (code "64") (name "pwm2") (class "Default")
      (node (ref "R6") (pin "1") (pinfunction "1_1") (pintype "unspecified"))
      (node (ref "U2") (pin "17") (pinfunction "B2_17") (pintype "unspecified"))
    )
    (net (code "65") (name "pwm3") (class "Default")
      (node (ref "U2") (pin "16") (pinfunction "B3_16") (pintype "unspecified"))
    )
    (net (code "66") (name "pwm4") (class "Default")
      (node (ref "U2") (pin "15") (pinfunction "B4_15") (pintype "unspecified"))
    )
    (net (code "67") (name "reset") (class "Default")
      (node (ref "C11") (pin "2") (pinfunction "2_2") (pintype "input"))
      (node (ref "Q1") (pin "3") (pinfunction "3_3") (pintype "input"))
      (node (ref "R19") (pin "2") (pinfunction "2_2") (pintype "input"))
      (node (ref "R22") (pin "1") (pinfunction "1_1") (pintype "input"))
      (node (ref "SW1") (pin "3") (pinfunction "3_3") (pintype "input"))
      (node (ref "SW1") (pin "4") (pinfunction "4_4") (pintype "input"))
      (node (ref "U1") (pin "3") (pinfunction "EN_3") (pintype "unspecified"))
    )
    (net (code "68") (name "rts") (class "Default")
      (node (ref "Q1") (pin "4") (pinfunction "4_4") (pintype "input"))
      (node (ref "R24") (pin "1") (pinfunction "1_1") (pintype "input"))
      (node (ref "U4") (pin "14") (pinfunction "RTS#_14") (pintype "unspecified"))
    )
    (net (code "69") (name "rx") (class "Default")
      (node (ref "U1") (pin "34") (pinfunction "RXD0_34") (pintype "unspecified"))
      (node (ref "U4") (pin "2") (pinfunction "TXD_2") (pintype "unspecified"))
    )
    (net (code "70") (name "scl") (class "Default")
      (node (ref "R16") (pin "1") (pinfunction "1_1") (pintype "input"))
      (node (ref "U1") (pin "36") (pinfunction "IO22_36") (pintype "unspecified"))
      (node (ref "U3") (pin "23") (pinfunction "SCL_23") (pintype "input"))
    )
    (net (code "71") (name "sda") (class "Default")
      (node (ref "R17") (pin "1") (pinfunction "1_1") (pintype "input"))
      (node (ref "U1") (pin "33") (pinfunction "IO21_33") (pintype "unspecified"))
      (node (ref "U3") (pin "24") (pinfunction "SDA_24") (pintype "unspecified"))
    )
    (net (code "72") (name "tx") (class "Default")
      (node (ref "U1") (pin "35") (pinfunction "TXD0_35") (pintype "unspecified"))
      (node (ref "U4") (pin "3") (pinfunction "RXD_3") (pintype "unspecified"))
    )
    (net (code "73") (name "unconnected-(U1-NC-Pad32)") (class "Default")
      (node (ref "U1") (pin "32") (pinfunction "NC_32") (pintype "unspecified+no_connect"))
    )
    (net (code "74") (name "unconnected-(U3-AUX_CL-Pad7)") (class "Default")
      (node (ref "U3") (pin "7") (pinfunction "AUX_CL_7") (pintype "unspecified+no_connect"))
    )
    (net (code "75") (name "unconnected-(U3-AUX_DA-Pad6)") (class "Default")
      (node (ref "U3") (pin "6") (pinfunction "AUX_DA_6") (pintype "unspecified+no_connect"))
    )
    (net (code "76") (name "unconnected-(U3-NC-Pad2)") (class "Default")
      (node (ref "U3") (pin "2") (pinfunction "NC_2") (pintype "unspecified+no_connect"))
    )
    (net (code "77") (name "unconnected-(U3-NC-Pad3)") (class "Default")
      (node (ref "U3") (pin "3") (pinfunction "NC_3") (pintype "unspecified+no_connect"))
    )
    (net (code "78") (name "unconnected-(U3-NC-Pad4)") (class "Default")
      (node (ref "U3") (pin "4") (pinfunction "NC_4") (pintype "unspecified+no_connect"))
    )
    (net (code "79") (name "unconnected-(U3-NC-Pad5)") (class "Default")
      (node (ref "U3") (pin "5") (pinfunction "NC_5") (pintype "unspecified+no_connect"))
    )
    (net (code "80") (name "unconnected-(U3-NC-Pad14)") (class "Default")
      (node (ref "U3") (pin "14") (pinfunction "NC_14") (pintype "unspecified+no_connect"))
    )
    (net (code "81") (name "unconnected-(U3-NC-Pad15)") (class "Default")
      (node (ref "U3") (pin "15") (pinfunction "NC_15") (pintype "unspecified+no_connect"))
    )
    (net (code "82") (name "unconnected-(U3-NC-Pad16)") (class "Default")
      (node (ref "U3") (pin "16") (pinfunction "NC_16") (pintype "unspecified+no_connect"))
    )
    (net (code "83") (name "unconnected-(U3-NC-Pad17)") (class "Default")
      (node (ref "U3") (pin "17") (pinfunction "NC_17") (pintype "unspecified+no_connect"))
    )
    (net (code "84") (name "unconnected-(U3-RESV-Pad19)") (class "Default")
      (node (ref "U3") (pin "19") (pinfunction "RESV_19") (pintype "unspecified+no_connect"))
    )
    (net (code "85") (name "unconnected-(U3-RESV-Pad21)") (class "Default")
      (node (ref "U3") (pin "21") (pinfunction "RESV_21") (pintype "unspecified+no_connect"))
    )
    (net (code "86") (name "unconnected-(U3-RESV-Pad22)") (class "Default")
      (node (ref "U3") (pin "22") (pinfunction "RESV_22") (pintype "unspecified+no_connect"))
    )
    (net (code "87") (name "unconnected-(U4-CTS#-Pad9)") (class "Default")
      (node (ref "U4") (pin "9") (pinfunction "CTS#_9") (pintype "unspecified+no_connect"))
    )
    (net (code "88") (name "unconnected-(U4-DCD#-Pad12)") (class "Default")
      (node (ref "U4") (pin "12") (pinfunction "DCD#_12") (pintype "unspecified+no_connect"))
    )
    (net (code "89") (name "unconnected-(U4-DSR#-Pad10)") (class "Default")
      (node (ref "U4") (pin "10") (pinfunction "DSR#_10") (pintype "unspecified+no_connect"))
    )
    (net (code "90") (name "unconnected-(U4-R232-Pad15)") (class "Default")
      (node (ref "U4") (pin "15") (pinfunction "R232_15") (pintype "unspecified+no_connect"))
    )
    (net (code "91") (name "unconnected-(U4-RI-Pad11)") (class "Default")
      (node (ref "U4") (pin "11") (pinfunction "RI_11") (pintype "unspecified+no_connect"))
    )
    (net (code "92") (name "unconnected-(U4-XI-Pad7)") (class "Default")
      (node (ref "U4") (pin "7") (pinfunction "XI_7") (pintype "unspecified+no_connect"))
    )
    (net (code "93") (name "unconnected-(U4-XO-Pad8)") (class "Default")
      (node (ref "U4") (pin "8") (pinfunction "XO_8") (pintype "unspecified+no_connect"))
    )
    (net (code "94") (name "unconnected-(USB1-ID-Pad4)") (class "Default")
      (node (ref "USB1") (pin "4") (pinfunction "ID_4") (pintype "input+no_connect"))
    )
    (net (code "95") (name "unconnected-(USB1-Pad0)") (class "Default")
      (node (ref "USB1") (pin "0") (pinfunction "0_0") (pintype "input"))
    )
    (net (code "96") (name "vn") (class "Default")
      (node (ref "U1") (pin "5") (pinfunction "SENSOR_VN_5") (pintype "unspecified"))
      (node (ref "VACANTPINS") (pin "5") (pinfunction "5_5") (pintype "unspecified"))
    )
    (net (code "97") (name "vp") (class "Default")
      (node (ref "U1") (pin "4") (pinfunction "SENSOR_VP_4") (pintype "unspecified"))
      (node (ref "VACANTPINS") (pin "6") (pinfunction "6_6") (pintype "unspecified"))
    )
    (net (code "98") (name "x2") (class "Default")
      (node (ref "U1") (pin "28") (pinfunction "IO17_28") (pintype "unspecified"))
      (node (ref "VACANTPINS") (pin "2") (pinfunction "2_2") (pintype "unspecified"))
    )
    (net (code "99") (name "x3") (class "Default")
      (node (ref "U1") (pin "30") (pinfunction "IO18_30") (pintype "unspecified"))
      (node (ref "VACANTPINS") (pin "3") (pinfunction "3_3") (pintype "unspecified"))
    )
    (net (code "100") (name "x4") (class "Default")
      (node (ref "U1") (pin "31") (pinfunction "IO19_31") (pintype "unspecified"))
      (node (ref "VACANTPINS") (pin "4") (pinfunction "4_4") (pintype "unspecified"))
    )
  )
)
